# avr_programming_shield_v12.net
KiCad netlist of a schematic drawn in EAGLE
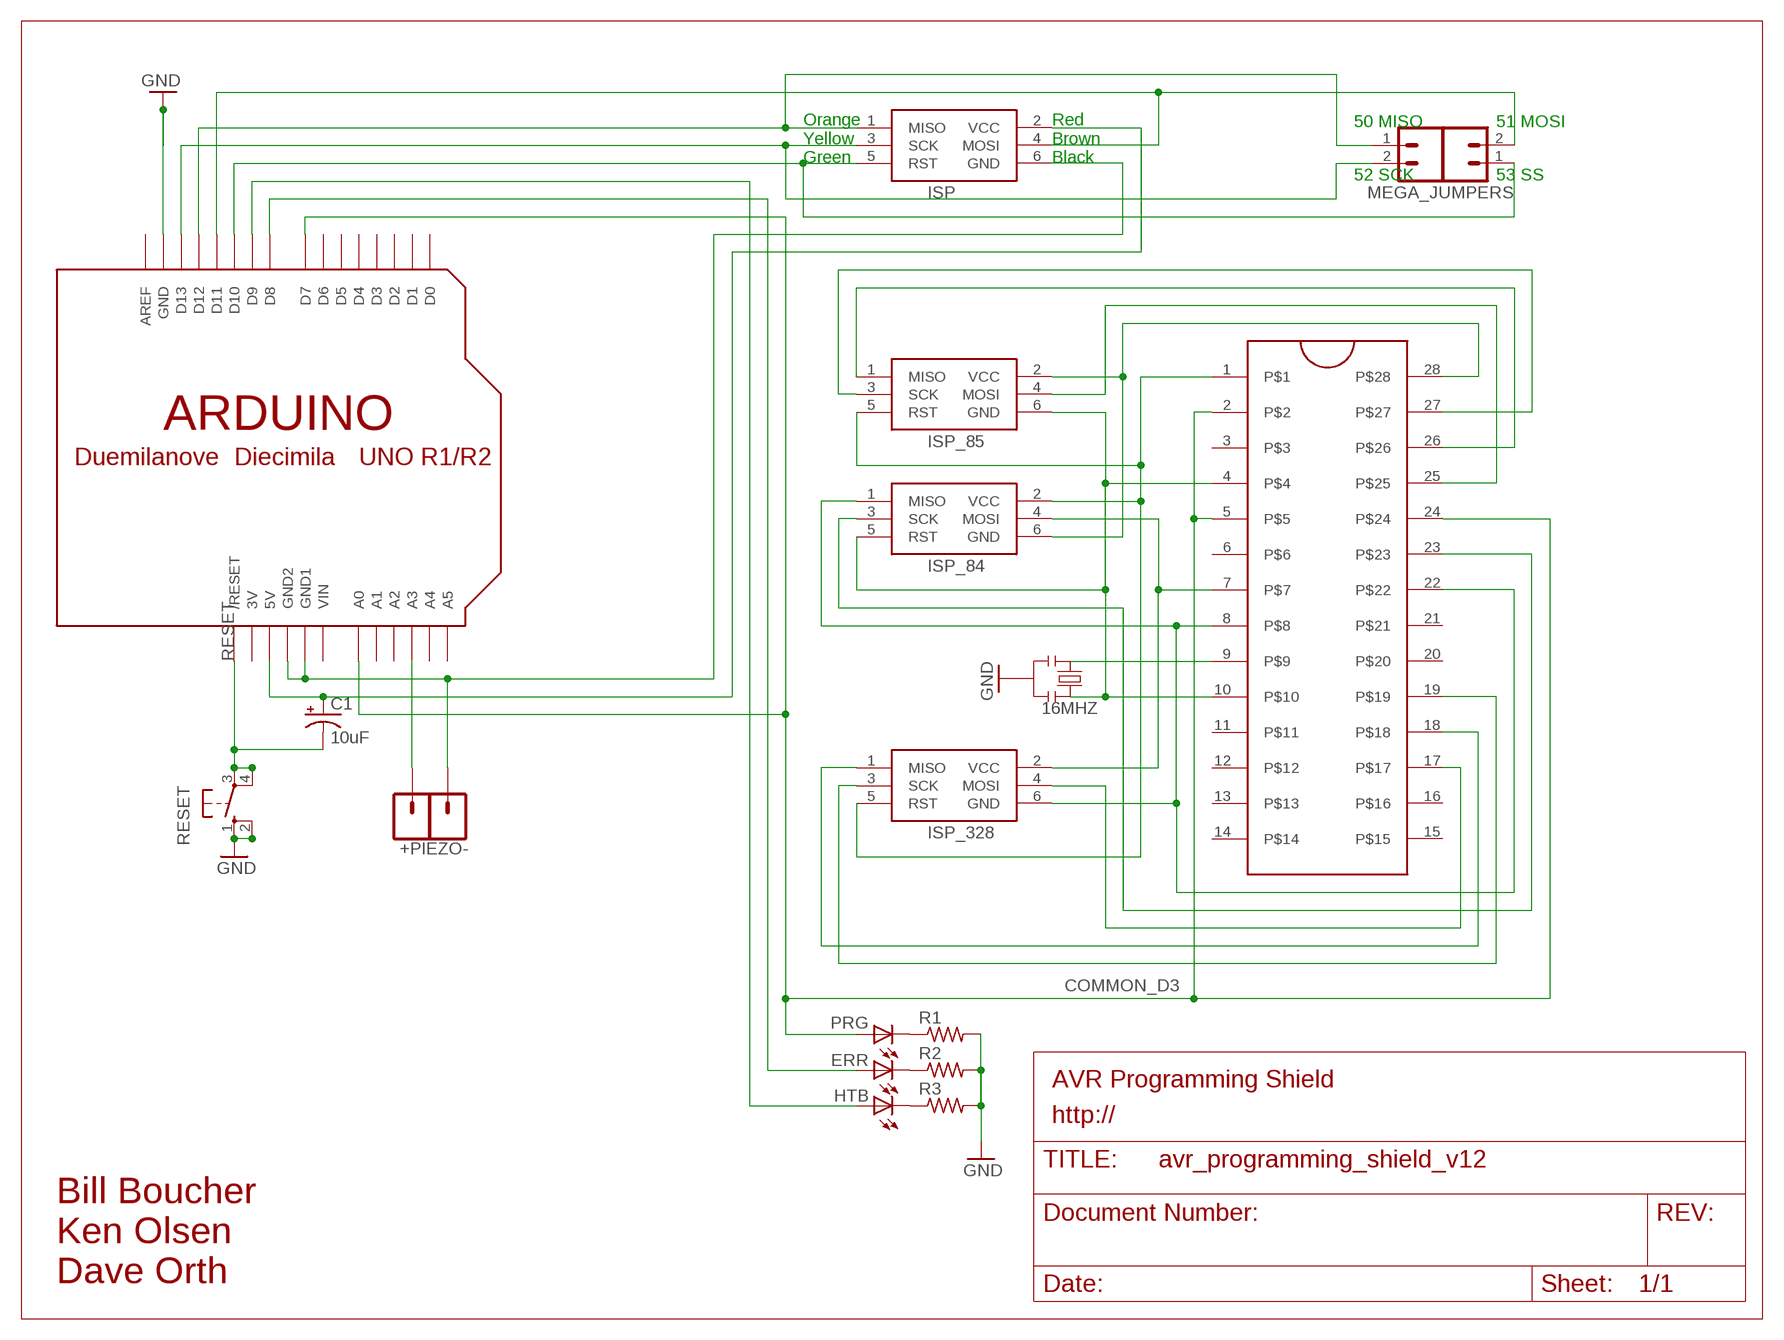
[diagram p0: schematic, sheet 1]

(export (version "E")
  (design (tool "Eeschema 10.0.6"))
  (components
    (comp (ref "+PIEZO-")
      (value "M01PTH")
      (footprint "eagle-import:1X01")
      (libsource (lib "eagle-import") (part "M01PTH"))
    )
    (comp (ref "16MHZ")
      (value "RESONATORPTH")
      (footprint "eagle-import:RESONATOR-PTH")
      (libsource (lib "eagle-import") (part "RESONATORPTH"))
    )
    (comp (ref "C1")
      (value "10uF")
      (footprint "eagle-import:CPOL-RADIAL-10UF-25V")
      (fields (field (name "MF") "ILLINOIS CAPACITOR,INC.") (field (name "MPN") "106TTA035M"))
      (libsource (lib "eagle-import") (part "CAP_POLPTH2"))
    )
    (comp (ref "ERR")
      (value "LED3MM")
      (footprint "eagle-import:LED3MM")
      (libsource (lib "eagle-import") (part "LED3MM"))
    )
    (comp (ref "HTB")
      (value "LED3MM")
      (footprint "eagle-import:LED3MM")
      (libsource (lib "eagle-import") (part "LED3MM"))
    )
    (comp (ref "ISP")
      (value "AVRISP-6")
      (footprint "eagle-import:AVRISP")
      (libsource (lib "eagle-import") (part "AVRISP-6"))
    )
    (comp (ref "ISP_84")
      (value "AVRISP-6")
      (footprint "eagle-import:AVRISP")
      (libsource (lib "eagle-import") (part "AVRISP-6"))
    )
    (comp (ref "ISP_85")
      (value "AVRISP-6")
      (footprint "eagle-import:AVRISP")
      (libsource (lib "eagle-import") (part "AVRISP-6"))
    )
    (comp (ref "ISP_328")
      (value "AVRISP-6")
      (footprint "eagle-import:AVRISP")
      (libsource (lib "eagle-import") (part "AVRISP-6"))
    )
    (comp (ref "JP2")
      (value "M02PTH")
      (footprint "eagle-import:1X02")
      (libsource (lib "eagle-import") (part "M02PTH"))
    )
    (comp (ref "JP4")
      (value "M01PTH")
      (footprint "eagle-import:1X01")
      (libsource (lib "eagle-import") (part "M01PTH"))
    )
    (comp (ref "MEGA_JUMPERS")
      (value "M02PTH")
      (footprint "eagle-import:1X02")
      (libsource (lib "eagle-import") (part "M02PTH"))
    )
    (comp (ref "PRG")
      (value "LED3MM")
      (footprint "eagle-import:LED3MM")
      (libsource (lib "eagle-import") (part "LED3MM"))
    )
    (comp (ref "R1")
      (value "R-US_0207/7")
      (footprint "eagle-import:0207_7")
      (libsource (lib "eagle-import") (part "R-US_0207/7"))
    )
    (comp (ref "R2")
      (value "R-US_0207/7")
      (footprint "eagle-import:0207_7")
      (libsource (lib "eagle-import") (part "R-US_0207/7"))
    )
    (comp (ref "R3")
      (value "R-US_0207/7")
      (footprint "eagle-import:0207_7")
      (libsource (lib "eagle-import") (part "R-US_0207/7"))
    )
    (comp (ref "RESET")
      (value "10-XX")
      (footprint "eagle-import:B3F-10XX")
      (fields
        (field (name "MPN") "B3F-1000")
        (field (name "MPN_1") "B3F-1000")
        (field (name "OC_NEWARK") "36M3542")
      )
      (libsource (lib "eagle-import") (part "10-XX"))
    )
    (comp (ref "U$4")
      (value "ZIFSOCKET-28-3ZIFFSOCKET-28-3")
      (footprint "eagle-import:DIL28-3-ZIF_SOCKET")
      (libsource (lib "eagle-import") (part "ZIFSOCKET-28-3ZIFFSOCKET-28-3"))
    )
    (comp (ref "U$5")
      (value "ARDUINO-NOHOLE")
      (footprint "eagle-import:ARDUINO-NOHOLE")
      (libsource (lib "eagle-import") (part "ARDUINO-NOHOLE"))
    )
  )
  (nets
    (net (code "1") (name "/3V") (class "Default")
      (node (ref "U$5") (pin "3V") (pinfunction "3V_3V") (pintype "power_in"))
    )
    (net (code "2") (name "/COMMON_D3") (class "Default")
      (node (ref "PRG") (pin "A") (pinfunction "A_A") (pintype "passive"))
      (node (ref "U$4") (pin "2") (pinfunction "P$2_2") (pintype "bidirectional"))
      (node (ref "U$4") (pin "24") (pinfunction "P$24_24") (pintype "bidirectional"))
      (node (ref "U$4") (pin "5") (pinfunction "P$5_5") (pintype "bidirectional"))
      (node (ref "U$5") (pin "A0") (pinfunction "A0_A0") (pintype "bidirectional"))
      (node (ref "U$5") (pin "D7") (pinfunction "D7_D7") (pintype "bidirectional"))
    )
    (net (code "3") (name "/RESET") (class "Default")
      (node (ref "C1") (pin "2") (pinfunction "-_2") (pintype "passive"))
      (node (ref "RESET") (pin "3") (pinfunction "P_3") (pintype "passive"))
      (node (ref "RESET") (pin "4") (pinfunction "P1_4") (pintype "passive"))
      (node (ref "U$5") (pin "RESET") (pinfunction "/RESET_RESET") (pintype "bidirectional"))
    )
    (net (code "4") (name "/VIN") (class "Default")
      (node (ref "U$5") (pin "VIN") (pinfunction "VIN_VIN") (pintype "power_in"))
    )
    (net (code "5") (name "GND") (class "Default")
      (node (ref "+PIEZO-") (pin "1") (pinfunction "1_1") (pintype "passive"))
      (node (ref "16MHZ") (pin "2") (pinfunction "2_2") (pintype "passive"))
      (node (ref "ISP") (pin "6") (pinfunction "GND_6") (pintype "power_in"))
      (node (ref "R1") (pin "2") (pinfunction "2_2") (pintype "passive"))
      (node (ref "R2") (pin "2") (pinfunction "2_2") (pintype "passive"))
      (node (ref "R3") (pin "2") (pinfunction "2_2") (pintype "passive"))
      (node (ref "RESET") (pin "1") (pinfunction "S_1") (pintype "passive"))
      (node (ref "RESET") (pin "2") (pinfunction "S1_2") (pintype "passive"))
      (node (ref "U$5") (pin "GND") (pinfunction "GND_GND") (pintype "power_in"))
      (node (ref "U$5") (pin "GND1") (pinfunction "GND1_GND1") (pintype "power_in"))
      (node (ref "U$5") (pin "GND2") (pinfunction "GND2_GND2") (pintype "power_in"))
    )
    (net (code "6") (name "Net-(C1-+)") (class "Default")
      (node (ref "C1") (pin "1") (pinfunction "+_1") (pintype "passive"))
      (node (ref "ISP") (pin "2") (pinfunction "VCC_2") (pintype "power_in"))
      (node (ref "U$5") (pin "5V") (pinfunction "5V_5V") (pintype "power_in"))
    )
    (net (code "7") (name "Net-(ERR-C)") (class "Default")
      (node (ref "ERR") (pin "K") (pinfunction "C_K") (pintype "passive"))
      (node (ref "R2") (pin "1") (pinfunction "1_1") (pintype "passive"))
    )
    (net (code "8") (name "Net-(ERR-PadA)") (class "Default")
      (node (ref "ERR") (pin "A") (pinfunction "A_A") (pintype "passive"))
      (node (ref "U$5") (pin "D8") (pinfunction "D8_D8") (pintype "bidirectional"))
    )
    (net (code "9") (name "Net-(HTB-C)") (class "Default")
      (node (ref "HTB") (pin "K") (pinfunction "C_K") (pintype "passive"))
      (node (ref "R3") (pin "1") (pinfunction "1_1") (pintype "passive"))
    )
    (net (code "10") (name "Net-(HTB-PadA)") (class "Default")
      (node (ref "HTB") (pin "A") (pinfunction "A_A") (pintype "passive"))
      (node (ref "U$5") (pin "D9") (pinfunction "D9_D9") (pintype "bidirectional"))
    )
    (net (code "11") (name "Net-(ISP-MISO)") (class "Default")
      (node (ref "ISP") (pin "1") (pinfunction "MISO_1") (pintype "input"))
      (node (ref "MEGA_JUMPERS") (pin "1") (pinfunction "1_1") (pintype "passive"))
      (node (ref "U$5") (pin "D12") (pinfunction "D12_D12") (pintype "bidirectional"))
    )
    (net (code "12") (name "Net-(ISP-MOSI)") (class "Default")
      (node (ref "ISP") (pin "4") (pinfunction "MOSI_4") (pintype "output"))
      (node (ref "JP2") (pin "2") (pinfunction "2_2") (pintype "passive"))
      (node (ref "U$5") (pin "D11") (pinfunction "D11_D11") (pintype "bidirectional"))
    )
    (net (code "13") (name "Net-(ISP-RST)") (class "Default")
      (node (ref "ISP") (pin "5") (pinfunction "RST_5") (pintype "output"))
      (node (ref "JP2") (pin "1") (pinfunction "1_1") (pintype "passive"))
      (node (ref "U$5") (pin "D10") (pinfunction "D10_D10") (pintype "bidirectional"))
    )
    (net (code "14") (name "Net-(ISP-SCK)") (class "Default")
      (node (ref "ISP") (pin "3") (pinfunction "SCK_3") (pintype "output"))
      (node (ref "MEGA_JUMPERS") (pin "2") (pinfunction "2_2") (pintype "passive"))
      (node (ref "U$5") (pin "D13") (pinfunction "D13_D13") (pintype "bidirectional"))
    )
    (net (code "15") (name "Net-(ISP_84-GND)") (class "Default")
      (node (ref "ISP_84") (pin "6") (pinfunction "GND_6") (pintype "power_in"))
      (node (ref "ISP_85") (pin "2") (pinfunction "VCC_2") (pintype "power_in"))
      (node (ref "U$4") (pin "28") (pinfunction "P$28_28") (pintype "bidirectional"))
    )
    (net (code "16") (name "Net-(ISP_84-RST)") (class "Default")
      (node (ref "16MHZ") (pin "3") (pinfunction "3_3") (pintype "passive"))
      (node (ref "ISP_84") (pin "5") (pinfunction "RST_5") (pintype "output"))
      (node (ref "ISP_85") (pin "6") (pinfunction "GND_6") (pintype "power_in"))
      (node (ref "U$4") (pin "10") (pinfunction "P$10_10") (pintype "bidirectional"))
      (node (ref "U$4") (pin "4") (pinfunction "P$4_4") (pintype "bidirectional"))
    )
    (net (code "17") (name "Net-(ISP_84-SCK)") (class "Default")
      (node (ref "ISP_84") (pin "3") (pinfunction "SCK_3") (pintype "output"))
      (node (ref "U$4") (pin "23") (pinfunction "P$23_23") (pintype "bidirectional"))
    )
    (net (code "18") (name "Net-(ISP_85-MISO)") (class "Default")
      (node (ref "ISP_85") (pin "1") (pinfunction "MISO_1") (pintype "input"))
      (node (ref "U$4") (pin "26") (pinfunction "P$26_26") (pintype "bidirectional"))
    )
    (net (code "19") (name "Net-(ISP_85-MOSI)") (class "Default")
      (node (ref "ISP_85") (pin "4") (pinfunction "MOSI_4") (pintype "output"))
      (node (ref "U$4") (pin "25") (pinfunction "P$25_25") (pintype "bidirectional"))
    )
    (net (code "20") (name "Net-(ISP_85-SCK)") (class "Default")
      (node (ref "ISP_85") (pin "3") (pinfunction "SCK_3") (pintype "output"))
      (node (ref "U$4") (pin "27") (pinfunction "P$27_27") (pintype "bidirectional"))
    )
    (net (code "21") (name "Net-(ISP_328-GND)") (class "Default")
      (node (ref "ISP_328") (pin "6") (pinfunction "GND_6") (pintype "power_in"))
      (node (ref "ISP_84") (pin "1") (pinfunction "MISO_1") (pintype "input"))
      (node (ref "U$4") (pin "22") (pinfunction "P$22_22") (pintype "bidirectional"))
      (node (ref "U$4") (pin "8") (pinfunction "P$8_8") (pintype "bidirectional"))
    )
    (net (code "22") (name "Net-(ISP_328-MISO)") (class "Default")
      (node (ref "ISP_328") (pin "1") (pinfunction "MISO_1") (pintype "input"))
      (node (ref "U$4") (pin "18") (pinfunction "P$18_18") (pintype "bidirectional"))
    )
    (net (code "23") (name "Net-(ISP_328-MOSI)") (class "Default")
      (node (ref "ISP_328") (pin "4") (pinfunction "MOSI_4") (pintype "output"))
      (node (ref "U$4") (pin "17") (pinfunction "P$17_17") (pintype "bidirectional"))
    )
    (net (code "24") (name "Net-(ISP_328-RST)") (class "Default")
      (node (ref "ISP_328") (pin "5") (pinfunction "RST_5") (pintype "output"))
      (node (ref "ISP_84") (pin "2") (pinfunction "VCC_2") (pintype "power_in"))
      (node (ref "ISP_85") (pin "5") (pinfunction "RST_5") (pintype "output"))
      (node (ref "U$4") (pin "1") (pinfunction "P$1_1") (pintype "bidirectional"))
    )
    (net (code "25") (name "Net-(ISP_328-SCK)") (class "Default")
      (node (ref "ISP_328") (pin "3") (pinfunction "SCK_3") (pintype "output"))
      (node (ref "U$4") (pin "19") (pinfunction "P$19_19") (pintype "bidirectional"))
    )
    (net (code "26") (name "Net-(ISP_328-VCC)") (class "Default")
      (node (ref "ISP_328") (pin "2") (pinfunction "VCC_2") (pintype "power_in"))
      (node (ref "ISP_84") (pin "4") (pinfunction "MOSI_4") (pintype "output"))
      (node (ref "U$4") (pin "7") (pinfunction "P$7_7") (pintype "bidirectional"))
    )
    (net (code "27") (name "Net-(JP4-Pad1)") (class "Default")
      (node (ref "JP4") (pin "1") (pinfunction "1_1") (pintype "passive"))
      (node (ref "U$5") (pin "A3") (pinfunction "A3_A3") (pintype "bidirectional"))
    )
    (net (code "28") (name "Net-(PRG-C)") (class "Default")
      (node (ref "PRG") (pin "K") (pinfunction "C_K") (pintype "passive"))
      (node (ref "R1") (pin "1") (pinfunction "1_1") (pintype "passive"))
    )
    (net (code "29") (name "Net-(U$4-P$9)") (class "Default")
      (node (ref "16MHZ") (pin "1") (pinfunction "1_1") (pintype "passive"))
      (node (ref "U$4") (pin "9") (pinfunction "P$9_9") (pintype "bidirectional"))
    )
    (net (code "30") (name "unconnected-(U$4-P$3-Pad3)") (class "Default")
      (node (ref "U$4") (pin "3") (pinfunction "P$3_3") (pintype "bidirectional"))
    )
    (net (code "31") (name "unconnected-(U$4-P$6-Pad6)") (class "Default")
      (node (ref "U$4") (pin "6") (pinfunction "P$6_6") (pintype "bidirectional"))
    )
    (net (code "32") (name "unconnected-(U$4-P$11-Pad11)") (class "Default")
      (node (ref "U$4") (pin "11") (pinfunction "P$11_11") (pintype "bidirectional"))
    )
    (net (code "33") (name "unconnected-(U$4-P$12-Pad12)") (class "Default")
      (node (ref "U$4") (pin "12") (pinfunction "P$12_12") (pintype "bidirectional"))
    )
    (net (code "34") (name "unconnected-(U$4-P$13-Pad13)") (class "Default")
      (node (ref "U$4") (pin "13") (pinfunction "P$13_13") (pintype "bidirectional"))
    )
    (net (code "35") (name "unconnected-(U$4-P$14-Pad14)") (class "Default")
      (node (ref "U$4") (pin "14") (pinfunction "P$14_14") (pintype "bidirectional"))
    )
    (net (code "36") (name "unconnected-(U$4-P$15-Pad15)") (class "Default")
      (node (ref "U$4") (pin "15") (pinfunction "P$15_15") (pintype "bidirectional"))
    )
    (net (code "37") (name "unconnected-(U$4-P$16-Pad16)") (class "Default")
      (node (ref "U$4") (pin "16") (pinfunction "P$16_16") (pintype "bidirectional"))
    )
    (net (code "38") (name "unconnected-(U$4-P$20-Pad20)") (class "Default")
      (node (ref "U$4") (pin "20") (pinfunction "P$20_20") (pintype "bidirectional"))
    )
    (net (code "39") (name "unconnected-(U$4-P$21-Pad21)") (class "Default")
      (node (ref "U$4") (pin "21") (pinfunction "P$21_21") (pintype "bidirectional"))
    )
    (net (code "40") (name "unconnected-(U$5-PadA1)") (class "Default")
      (node (ref "U$5") (pin "A1") (pinfunction "A1_A1") (pintype "bidirectional"))
    )
    (net (code "41") (name "unconnected-(U$5-PadA2)") (class "Default")
      (node (ref "U$5") (pin "A2") (pinfunction "A2_A2") (pintype "bidirectional"))
    )
    (net (code "42") (name "unconnected-(U$5-PadA4)") (class "Default")
      (node (ref "U$5") (pin "A4") (pinfunction "A4_A4") (pintype "bidirectional"))
    )
    (net (code "43") (name "unconnected-(U$5-PadA5)") (class "Default")
      (node (ref "U$5") (pin "A5") (pinfunction "A5_A5") (pintype "bidirectional"))
    )
    (net (code "44") (name "unconnected-(U$5-PadAREF)") (class "Default")
      (node (ref "U$5") (pin "AREF") (pinfunction "AREF_AREF") (pintype "bidirectional"))
    )
    (net (code "45") (name "unconnected-(U$5-PadD0)") (class "Default")
      (node (ref "U$5") (pin "D0") (pinfunction "D0_D0") (pintype "bidirectional"))
    )
    (net (code "46") (name "unconnected-(U$5-PadD1)") (class "Default")
      (node (ref "U$5") (pin "D1") (pinfunction "D1_D1") (pintype "bidirectional"))
    )
    (net (code "47") (name "unconnected-(U$5-PadD2)") (class "Default")
      (node (ref "U$5") (pin "D2") (pinfunction "D2_D2") (pintype "bidirectional"))
    )
    (net (code "48") (name "unconnected-(U$5-PadD3)") (class "Default")
      (node (ref "U$5") (pin "D3") (pinfunction "D3_D3") (pintype "bidirectional"))
    )
    (net (code "49") (name "unconnected-(U$5-PadD4)") (class "Default")
      (node (ref "U$5") (pin "D4") (pinfunction "D4_D4") (pintype "bidirectional"))
    )
    (net (code "50") (name "unconnected-(U$5-PadD5)") (class "Default")
      (node (ref "U$5") (pin "D5") (pinfunction "D5_D5") (pintype "bidirectional"))
    )
    (net (code "51") (name "unconnected-(U$5-PadD6)") (class "Default")
      (node (ref "U$5") (pin "D6") (pinfunction "D6_D6") (pintype "bidirectional"))
    )
  )
)
